# Display.net
KiCad netlist of a schematic drawn in Altium Designer
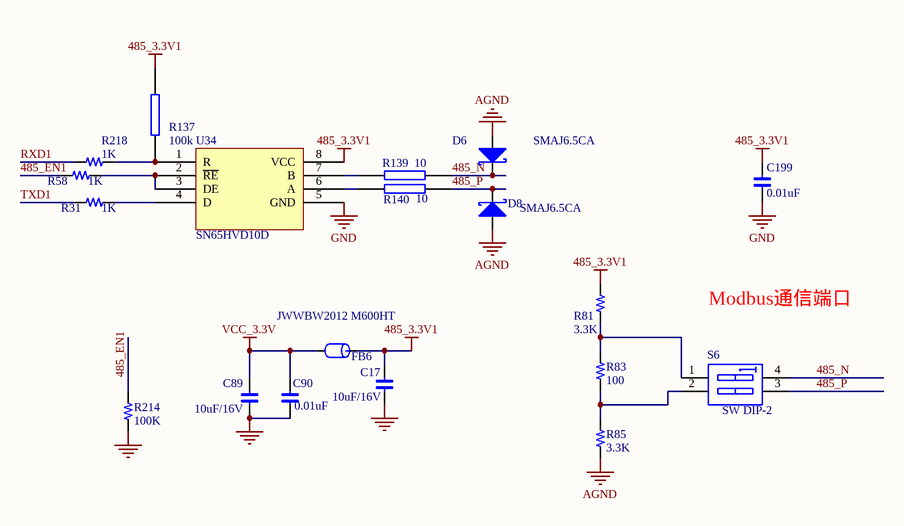
[diagram p0: Display.SchDoc]

(export (version "E")
  (design (tool "Eeschema 10.0.6"))
  (components
    (comp (ref "C17")
      (value "10uF/16V")
      (footprint "0805C")
      (description "C")
      (libsource (lib "Schlib_20110825") (part "C"))
    )
    (comp (ref "C89")
      (value "10uF/16V")
      (footprint "0805C")
      (description "C")
      (libsource (lib "Schlib_20110825") (part "C"))
    )
    (comp (ref "C90")
      (value "0.01uF")
      (footprint "0603C")
      (description "C")
      (libsource (lib "Schlib_20110825") (part "C"))
    )
    (comp (ref "C199")
      (value "0.01uF")
      (footprint "0603C")
      (description "C")
      (libsource (lib "Schlib_20110825") (part "C"))
    )
    (comp (ref "D6")
      (value "SMAJ6.5CA")
      (footprint "SMA")
      (description "Schottky Diode")
      (libsource (lib "*") (part "DIODE S"))
    )
    (comp (ref "D8")
      (value "SMAJ6.5CA")
      (footprint "SMA")
      (description "Schottky Diode")
      (libsource (lib "*") (part "DIODE S"))
    )
    (comp (ref "FB6")
      (value "JWWBW2012 M600HT")
      (footprint "0805CZ")
      (libsource (lib "Schlib_20110825") (part "FB"))
    )
    (comp (ref "R31") (value "1K") (footprint "0603R") (description "R") (libsource (lib "JRJ_1") (part "R")))
    (comp (ref "R58") (value "1K") (footprint "0603R") (description "R") (libsource (lib "JRJ_1") (part "R")))
    (comp (ref "R81")
      (value "3.3K")
      (footprint "0603R")
      (description "R")
      (libsource (lib "JRJ_1") (part "R"))
    )
    (comp (ref "R83")
      (value "100")
      (footprint "0603R")
      (description "R")
      (libsource (lib "JRJ_1") (part "R"))
    )
    (comp (ref "R85")
      (value "3.3K")
      (footprint "0603R")
      (description "R")
      (libsource (lib "JRJ_1") (part "R"))
    )
    (comp (ref "R137") (value "100k") (footprint "0603R") (libsource (lib "*") (part "RES2")))
    (comp (ref "R139") (value "10") (footprint "1206R") (libsource (lib "*") (part "RES2")))
    (comp (ref "R140") (value "10") (footprint "1206R") (libsource (lib "*") (part "RES2")))
    (comp (ref "R214")
      (value "100K")
      (footprint "0603R")
      (description "R")
      (libsource (lib "JRJ_1") (part "R"))
    )
    (comp (ref "R218")
      (value "1K")
      (footprint "0603R")
      (description "R")
      (libsource (lib "JRJ_1") (part "R"))
    )
    (comp (ref "S6")
      (value "SW DIP-2")
      (footprint "DIP-4")
      (description "DIP Switch, 2 Position, SPST")
      (fields (field (name "PUBLISHER") "Altium Limited"))
      (libsource (lib "Miscellaneous Devices") (part "SW DIP-2"))
    )
    (comp (ref "U34")
      (value "SN65HVD10D")
      (footprint "Pcblib_20110825:so-8")
      (libsource (lib "Schlib1") (part "SN65HVD06D"))
    )
  )
  (nets
    (net (code "1") (name "/485_EN1") (class "Default")
      (node (ref "R214") (pin "2") (pintype "passive"))
      (node (ref "R58") (pin "2") (pintype "passive"))
    )
    (net (code "2") (name "/485_N") (class "Default")
      (node (ref "D6") (pin "K") (pinfunction "K_K") (pintype "passive"))
      (node (ref "R139") (pin "1") (pinfunction "1_1") (pintype "passive"))
      (node (ref "S6") (pin "4") (pinfunction "B1_4") (pintype "passive"))
    )
    (net (code "3") (name "/485_P") (class "Default")
      (node (ref "D8") (pin "K") (pinfunction "K_K") (pintype "passive"))
      (node (ref "R140") (pin "1") (pinfunction "1_1") (pintype "passive"))
      (node (ref "S6") (pin "3") (pinfunction "B2_3") (pintype "passive"))
    )
    (net (code "4") (name "/RXD1") (class "Default") (node (ref "R218") (pin "2") (pintype "passive")))
    (net (code "5") (name "/TXD1") (class "Default") (node (ref "R31") (pin "2") (pintype "passive")))
    (net (code "6") (name "485_3.3V1") (class "Default")
      (node (ref "C17") (pin "2") (pintype "passive"))
      (node (ref "C199") (pin "2") (pintype "passive"))
      (node (ref "FB6") (pin "1") (pintype "passive"))
      (node (ref "R137") (pin "2") (pinfunction "2_2") (pintype "passive"))
      (node (ref "R81") (pin "2") (pintype "passive"))
      (node (ref "U34") (pin "8") (pinfunction "VCC_8") (pintype "passive"))
    )
    (net (code "7") (name "AGND") (class "Default")
      (node (ref "D6") (pin "A") (pinfunction "A_A") (pintype "passive"))
      (node (ref "D8") (pin "A") (pinfunction "A_A") (pintype "passive"))
      (node (ref "R85") (pin "1") (pintype "passive"))
    )
    (net (code "8") (name "GND") (class "Default")
      (node (ref "C17") (pin "1") (pintype "passive"))
      (node (ref "C199") (pin "1") (pintype "passive"))
      (node (ref "C89") (pin "1") (pintype "passive"))
      (node (ref "C90") (pin "1") (pintype "passive"))
      (node (ref "R214") (pin "1") (pintype "passive"))
      (node (ref "U34") (pin "5") (pinfunction "GND_5") (pintype "passive"))
    )
    (net (code "9") (name "Net-(S6-A1)") (class "Default")
      (node (ref "R81") (pin "1") (pintype "passive"))
      (node (ref "R83") (pin "2") (pintype "passive"))
      (node (ref "S6") (pin "1") (pinfunction "A1_1") (pintype "passive"))
    )
    (net (code "10") (name "Net-(S6-A2)") (class "Default")
      (node (ref "R83") (pin "1") (pintype "passive"))
      (node (ref "R85") (pin "2") (pintype "passive"))
      (node (ref "S6") (pin "2") (pinfunction "A2_2") (pintype "passive"))
    )
    (net (code "11") (name "Net-(U34-A)") (class "Default")
      (node (ref "R140") (pin "2") (pinfunction "2_2") (pintype "passive"))
      (node (ref "U34") (pin "6") (pinfunction "A_6") (pintype "passive"))
    )
    (net (code "12") (name "Net-(U34-B)") (class "Default")
      (node (ref "R139") (pin "2") (pinfunction "2_2") (pintype "passive"))
      (node (ref "U34") (pin "7") (pinfunction "B_7") (pintype "passive"))
    )
    (net (code "13") (name "Net-(U34-D)") (class "Default")
      (node (ref "R31") (pin "1") (pintype "passive"))
      (node (ref "U34") (pin "4") (pinfunction "D_4") (pintype "passive"))
    )
    (net (code "14") (name "Net-(U34-DE)") (class "Default")
      (node (ref "R58") (pin "1") (pintype "passive"))
      (node (ref "U34") (pin "2") (pinfunction "~{RE}_2") (pintype "passive"))
      (node (ref "U34") (pin "3") (pinfunction "DE_3") (pintype "passive"))
    )
    (net (code "15") (name "Net-(U34-R)") (class "Default")
      (node (ref "R137") (pin "1") (pinfunction "1_1") (pintype "passive"))
      (node (ref "R218") (pin "1") (pintype "passive"))
      (node (ref "U34") (pin "1") (pinfunction "R_1") (pintype "passive"))
    )
    (net (code "16") (name "VCC_3.3V") (class "Default")
      (node (ref "C89") (pin "2") (pintype "passive"))
      (node (ref "C90") (pin "2") (pintype "passive"))
      (node (ref "FB6") (pin "2") (pintype "passive"))
    )
  )
)
